# PMIC_RK809_RK3566_LPDDR4.net
KiCad netlist of a schematic drawn in Altium Designer
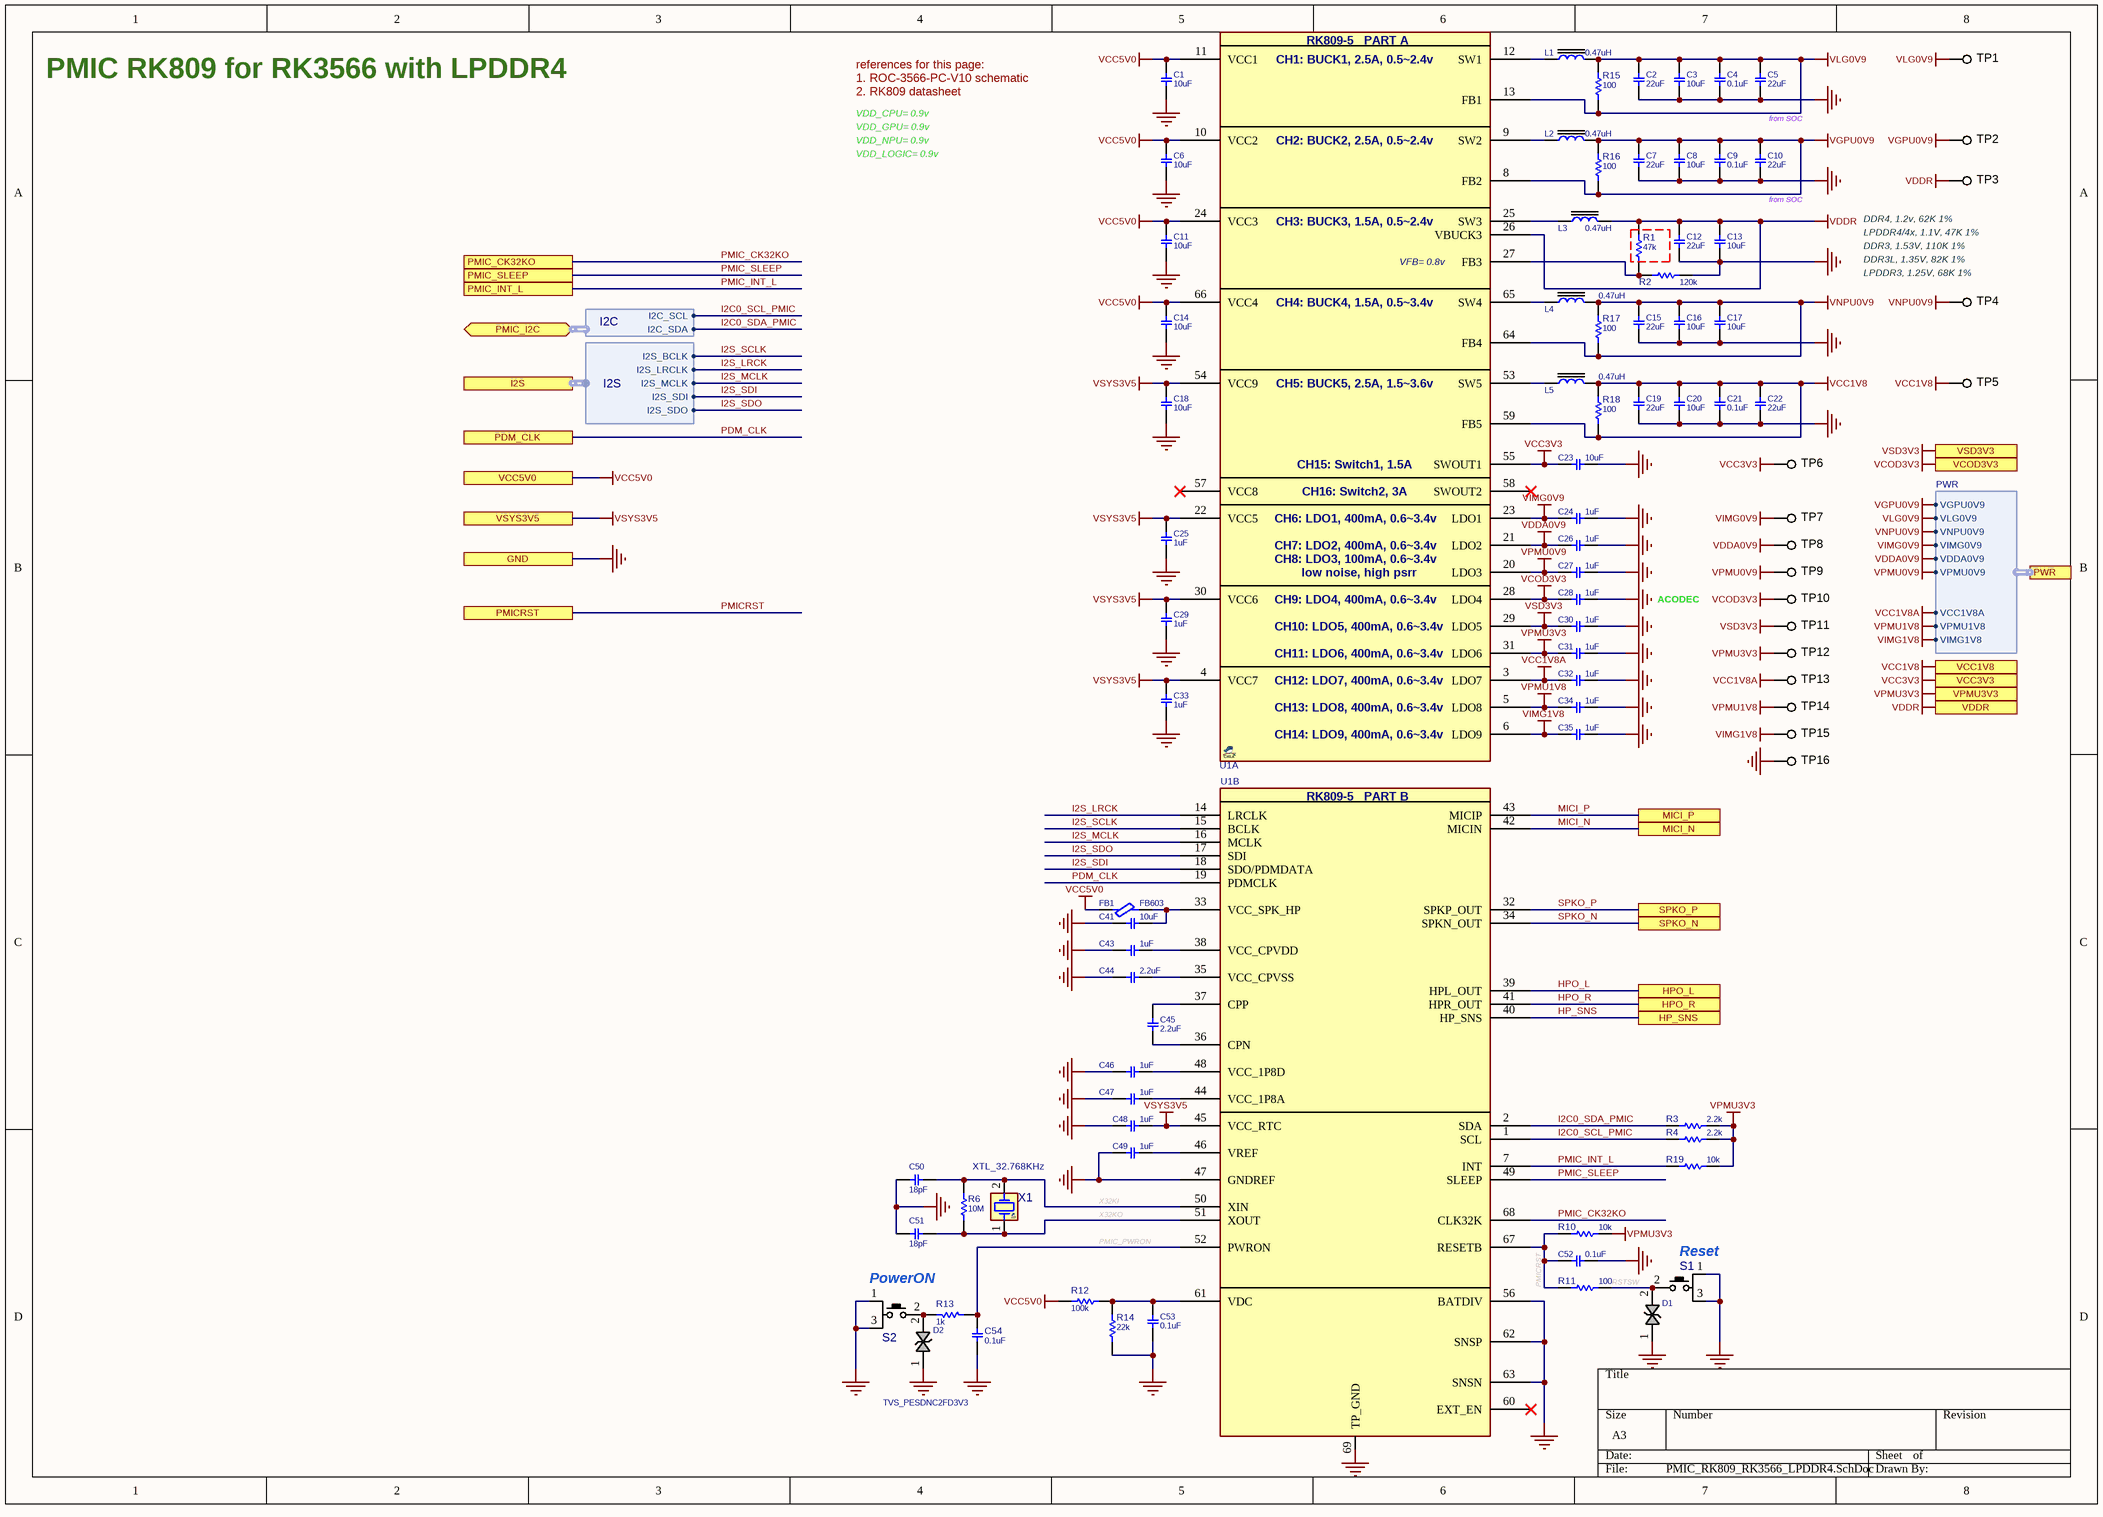
[diagram p0: PMIC_RK809_RK3566_LPDDR4.SchDoc]

(export (version "E")
  (design (tool "Eeschema 10.0.6"))
  (components
    (comp (ref "C1")
      (value "10uF")
      (footprint "C0402")
      (description "CAP, MLCC")
      (fields (field (name "MANF_P#") "CL05A106MP5NUNC") (field (name "MANF") "Samsung"))
      (libsource (lib "passive_smd") (part "CAP_SMD_MLCC"))
    )
    (comp (ref "C2")
      (value "22uF")
      (footprint "C0402")
      (description "CAP, MLCC")
      (fields (field (name "MANF_P#") "GRM158R61A226ME15") (field (name "MANF") "Murata"))
      (libsource (lib "passive_smd") (part "CAP_SMD_MLCC"))
    )
    (comp (ref "C3")
      (value "10uF")
      (footprint "C0402")
      (description "CAP, MLCC")
      (fields (field (name "MANF_P#") "CL05A106MP5NUNC") (field (name "MANF") "Samsung"))
      (libsource (lib "passive_smd") (part "CAP_SMD_MLCC"))
    )
    (comp (ref "C4")
      (value "0.1uF")
      (footprint "C0402")
      (description "CAP, MLCC")
      (fields (field (name "MANF_P#") "GRM155R61E104") (field (name "MANF") "Murata"))
      (libsource (lib "passive_smd") (part "CAP_SMD_MLCC"))
    )
    (comp (ref "C5")
      (value "22uF")
      (footprint "C0402")
      (description "CAP, MLCC")
      (fields (field (name "MANF_P#") "GRM158R61A226ME15") (field (name "MANF") "Murata"))
      (libsource (lib "passive_smd") (part "CAP_SMD_MLCC"))
    )
    (comp (ref "C6")
      (value "10uF")
      (footprint "C0402")
      (description "CAP, MLCC")
      (fields (field (name "MANF_P#") "CL05A106MP5NUNC") (field (name "MANF") "Samsung"))
      (libsource (lib "passive_smd") (part "CAP_SMD_MLCC"))
    )
    (comp (ref "C7")
      (value "22uF")
      (footprint "C0402")
      (description "CAP, MLCC")
      (fields (field (name "MANF_P#") "GRM158R61A226ME15") (field (name "MANF") "Murata"))
      (libsource (lib "passive_smd") (part "CAP_SMD_MLCC"))
    )
    (comp (ref "C8")
      (value "10uF")
      (footprint "C0402")
      (description "CAP, MLCC")
      (fields (field (name "MANF_P#") "CL05A106MP5NUNC") (field (name "MANF") "Samsung"))
      (libsource (lib "passive_smd") (part "CAP_SMD_MLCC"))
    )
    (comp (ref "C9")
      (value "0.1uF")
      (footprint "C0402")
      (description "CAP, MLCC")
      (fields (field (name "MANF_P#") "GRM155R61E104") (field (name "MANF") "Murata"))
      (libsource (lib "passive_smd") (part "CAP_SMD_MLCC"))
    )
    (comp (ref "C10")
      (value "22uF")
      (footprint "C0402")
      (description "CAP, MLCC")
      (fields (field (name "MANF_P#") "GRM158R61A226ME15") (field (name "MANF") "Murata"))
      (libsource (lib "passive_smd") (part "CAP_SMD_MLCC"))
    )
    (comp (ref "C11")
      (value "10uF")
      (footprint "C0402")
      (description "CAP, MLCC")
      (fields (field (name "MANF_P#") "CL05A106MP5NUNC") (field (name "MANF") "Samsung"))
      (libsource (lib "passive_smd") (part "CAP_SMD_MLCC"))
    )
    (comp (ref "C12")
      (value "22uF")
      (footprint "C0402")
      (description "CAP, MLCC")
      (fields (field (name "MANF_P#") "GRM158R61A226ME15") (field (name "MANF") "Murata"))
      (libsource (lib "passive_smd") (part "CAP_SMD_MLCC"))
    )
    (comp (ref "C13")
      (value "10uF")
      (footprint "C0402")
      (description "CAP, MLCC")
      (fields (field (name "MANF_P#") "CL05A106MP5NUNC") (field (name "MANF") "Samsung"))
      (libsource (lib "passive_smd") (part "CAP_SMD_MLCC"))
    )
    (comp (ref "C14")
      (value "10uF")
      (footprint "C0402")
      (description "CAP, MLCC")
      (fields (field (name "MANF_P#") "CL05A106MP5NUNC") (field (name "MANF") "Samsung"))
      (libsource (lib "passive_smd") (part "CAP_SMD_MLCC"))
    )
    (comp (ref "C15")
      (value "22uF")
      (footprint "C0402")
      (description "CAP, MLCC")
      (fields (field (name "MANF_P#") "GRM158R61A226ME15") (field (name "MANF") "Murata"))
      (libsource (lib "passive_smd") (part "CAP_SMD_MLCC"))
    )
    (comp (ref "C16")
      (value "10uF")
      (footprint "C0402")
      (description "CAP, MLCC")
      (fields (field (name "MANF_P#") "CL05A106MP5NUNC") (field (name "MANF") "Samsung"))
      (libsource (lib "passive_smd") (part "CAP_SMD_MLCC"))
    )
    (comp (ref "C17")
      (value "10uF")
      (footprint "C0402")
      (description "CAP, MLCC")
      (fields (field (name "MANF_P#") "CL05A106MP5NUNC") (field (name "MANF") "Samsung"))
      (libsource (lib "passive_smd") (part "CAP_SMD_MLCC"))
    )
    (comp (ref "C18")
      (value "10uF")
      (footprint "C0402")
      (description "CAP, MLCC")
      (fields (field (name "MANF_P#") "CL05A106MP5NUNC") (field (name "MANF") "Samsung"))
      (libsource (lib "passive_smd") (part "CAP_SMD_MLCC"))
    )
    (comp (ref "C19")
      (value "22uF")
      (footprint "C0402")
      (description "CAP, MLCC")
      (fields (field (name "MANF_P#") "GRM158R61A226ME15") (field (name "MANF") "Murata"))
      (libsource (lib "passive_smd") (part "CAP_SMD_MLCC"))
    )
    (comp (ref "C20")
      (value "10uF")
      (footprint "C0402")
      (description "CAP, MLCC")
      (fields (field (name "MANF_P#") "CL05A106MP5NUNC") (field (name "MANF") "Samsung"))
      (libsource (lib "passive_smd") (part "CAP_SMD_MLCC"))
    )
    (comp (ref "C21")
      (value "0.1uF")
      (footprint "C0402")
      (description "CAP, MLCC")
      (fields (field (name "MANF_P#") "GRM155R61E104") (field (name "MANF") "Murata"))
      (libsource (lib "passive_smd") (part "CAP_SMD_MLCC"))
    )
    (comp (ref "C22")
      (value "22uF")
      (footprint "C0402")
      (description "CAP, MLCC")
      (fields (field (name "MANF_P#") "GRM158R61A226ME15") (field (name "MANF") "Murata"))
      (libsource (lib "passive_smd") (part "CAP_SMD_MLCC"))
    )
    (comp (ref "C23")
      (value "10uF")
      (footprint "C0402")
      (description "CAP, MLCC")
      (fields (field (name "MANF_P#") "CL05A106MP5NUNC") (field (name "MANF") "Samsung"))
      (libsource (lib "passive_smd") (part "CAP_SMD_MLCC"))
    )
    (comp (ref "C24")
      (value "1uF")
      (footprint "C0402")
      (description "CAP, MLCC")
      (fields (field (name "MANF_P#") "CL05A105KO5NNND") (field (name "MANF") "Samsung"))
      (libsource (lib "passive_smd") (part "CAP_SMD_MLCC"))
    )
    (comp (ref "C25")
      (value "1uF")
      (footprint "C0402")
      (description "CAP, MLCC")
      (fields (field (name "MANF_P#") "CL05A105KO5NNND") (field (name "MANF") "Samsung"))
      (libsource (lib "passive_smd") (part "CAP_SMD_MLCC"))
    )
    (comp (ref "C26")
      (value "1uF")
      (footprint "C0402")
      (description "CAP, MLCC")
      (fields (field (name "MANF_P#") "CL05A105KO5NNND") (field (name "MANF") "Samsung"))
      (libsource (lib "passive_smd") (part "CAP_SMD_MLCC"))
    )
    (comp (ref "C27")
      (value "1uF")
      (footprint "C0402")
      (description "CAP, MLCC")
      (fields (field (name "MANF_P#") "CL05A105KO5NNND") (field (name "MANF") "Samsung"))
      (libsource (lib "passive_smd") (part "CAP_SMD_MLCC"))
    )
    (comp (ref "C28")
      (value "1uF")
      (footprint "C0402")
      (description "CAP, MLCC")
      (fields (field (name "MANF_P#") "CL05A105KO5NNND") (field (name "MANF") "Samsung"))
      (libsource (lib "passive_smd") (part "CAP_SMD_MLCC"))
    )
    (comp (ref "C29")
      (value "1uF")
      (footprint "C0402")
      (description "CAP, MLCC")
      (fields (field (name "MANF_P#") "CL05A105KO5NNND") (field (name "MANF") "Samsung"))
      (libsource (lib "passive_smd") (part "CAP_SMD_MLCC"))
    )
    (comp (ref "C30")
      (value "1uF")
      (footprint "C0402")
      (description "CAP, MLCC")
      (fields (field (name "MANF_P#") "CL05A105KO5NNND") (field (name "MANF") "Samsung"))
      (libsource (lib "passive_smd") (part "CAP_SMD_MLCC"))
    )
    (comp (ref "C31")
      (value "1uF")
      (footprint "C0402")
      (description "CAP, MLCC")
      (fields (field (name "MANF_P#") "CL05A105KO5NNND") (field (name "MANF") "Samsung"))
      (libsource (lib "passive_smd") (part "CAP_SMD_MLCC"))
    )
    (comp (ref "C32")
      (value "1uF")
      (footprint "C0402")
      (description "CAP, MLCC")
      (fields (field (name "MANF_P#") "CL05A105KO5NNND") (field (name "MANF") "Samsung"))
      (libsource (lib "passive_smd") (part "CAP_SMD_MLCC"))
    )
    (comp (ref "C33")
      (value "1uF")
      (footprint "C0402")
      (description "CAP, MLCC")
      (fields (field (name "MANF_P#") "CL05A105KO5NNND") (field (name "MANF") "Samsung"))
      (libsource (lib "passive_smd") (part "CAP_SMD_MLCC"))
    )
    (comp (ref "C34")
      (value "1uF")
      (footprint "C0402")
      (description "CAP, MLCC")
      (fields (field (name "MANF_P#") "CL05A105KO5NNND") (field (name "MANF") "Samsung"))
      (libsource (lib "passive_smd") (part "CAP_SMD_MLCC"))
    )
    (comp (ref "C35")
      (value "1uF")
      (footprint "C0402")
      (description "CAP, MLCC")
      (fields (field (name "MANF_P#") "CL05A105KO5NNND") (field (name "MANF") "Samsung"))
      (libsource (lib "passive_smd") (part "CAP_SMD_MLCC"))
    )
    (comp (ref "C41")
      (value "10uF")
      (footprint "C0402")
      (description "CAP, MLCC")
      (fields (field (name "MANF_P#") "CL05A106MP5NUNC") (field (name "MANF") "Samsung"))
      (libsource (lib "passive_smd") (part "CAP_SMD_MLCC"))
    )
    (comp (ref "C43")
      (value "1uF")
      (footprint "C0402")
      (description "CAP, MLCC")
      (fields (field (name "MANF_P#") "CL05A105KO5NNND") (field (name "MANF") "Samsung"))
      (libsource (lib "passive_smd") (part "CAP_SMD_MLCC"))
    )
    (comp (ref "C44")
      (value "2.2uF")
      (footprint "C0402")
      (description "CAP, MLCC")
      (fields (field (name "MANF_P#") "CL05A225MP5NNNC") (field (name "MANF") "Samsung"))
      (libsource (lib "passive_smd") (part "CAP_SMD_MLCC"))
    )
    (comp (ref "C45")
      (value "2.2uF")
      (footprint "C0402")
      (description "CAP, MLCC")
      (fields (field (name "MANF_P#") "CL05A225MP5NNNC") (field (name "MANF") "Samsung"))
      (libsource (lib "passive_smd") (part "CAP_SMD_MLCC"))
    )
    (comp (ref "C46")
      (value "1uF")
      (footprint "C0402")
      (description "CAP, MLCC")
      (fields (field (name "MANF_P#") "CL05A105KO5NNND") (field (name "MANF") "Samsung"))
      (libsource (lib "passive_smd") (part "CAP_SMD_MLCC"))
    )
    (comp (ref "C47")
      (value "1uF")
      (footprint "C0402")
      (description "CAP, MLCC")
      (fields (field (name "MANF_P#") "CL05A105KO5NNND") (field (name "MANF") "Samsung"))
      (libsource (lib "passive_smd") (part "CAP_SMD_MLCC"))
    )
    (comp (ref "C48")
      (value "1uF")
      (footprint "C0402")
      (description "CAP, MLCC")
      (fields (field (name "MANF_P#") "CL05A105KO5NNND") (field (name "MANF") "Samsung"))
      (libsource (lib "passive_smd") (part "CAP_SMD_MLCC"))
    )
    (comp (ref "C49")
      (value "1uF")
      (footprint "C0402")
      (description "CAP, MLCC")
      (fields (field (name "MANF_P#") "CL05A105KO5NNND") (field (name "MANF") "Samsung"))
      (libsource (lib "passive_smd") (part "CAP_SMD_MLCC"))
    )
    (comp (ref "C50")
      (value "18pF")
      (footprint "C0402")
      (description "CAP, MLCC")
      (fields (field (name "MANF_P#") "CC0402JRNPO9BN180") (field (name "MANF") "Yageo"))
      (libsource (lib "mlcc_smd_passive") (part "CAP_SMD_MLCC"))
    )
    (comp (ref "C51")
      (value "18pF")
      (footprint "C0402")
      (description "CAP, MLCC")
      (fields (field (name "MANF_P#") "CC0402JRNPO9BN180") (field (name "MANF") "Yageo"))
      (libsource (lib "mlcc_smd_passive") (part "CAP_SMD_MLCC"))
    )
    (comp (ref "C52")
      (value "0.1uF")
      (footprint "C0402")
      (description "CAP, MLCC")
      (fields (field (name "MANF_P#") "GRM155R61E104") (field (name "MANF") "Murata"))
      (libsource (lib "passive_smd") (part "CAP_SMD_MLCC"))
    )
    (comp (ref "C53")
      (value "0.1uF")
      (footprint "C0402")
      (description "CAP, MLCC")
      (fields (field (name "MANF_P#") "GRM155R61E104") (field (name "MANF") "Murata"))
      (libsource (lib "passive_smd") (part "CAP_SMD_MLCC"))
    )
    (comp (ref "C54")
      (value "0.1uF")
      (footprint "C0402")
      (description "CAP, MLCC")
      (fields (field (name "MANF_P#") "GRM155R61E104") (field (name "MANF") "Murata"))
      (libsource (lib "mlcc_smd_passive") (part "CAP_SMD_MLCC_100n50TDK"))
    )
    (comp (ref "D1")
      (value "TVS_PESDNC2FD3V3")
      (footprint "ESD0402")
      (description "TVS, ESD PROTECT, Bidirectional")
      (fields (field (name "MANF_P#") "PESDNC2FD3V3BS"))
      (libsource (lib "protect_tvs_esd_fuse") (part "TVS_PESDNC2FD3V3"))
    )
    (comp (ref "D2")
      (value "TVS_PESDNC2FD3V3")
      (footprint "ESD0402")
      (description "TVS, ESD PROTECT, Bidirectional")
      (fields (field (name "MANF_P#") "PESDNC2FD3V3BS"))
      (libsource (lib "protect_tvs_esd_fuse") (part "TVS_PESDNC2FD3V3"))
    )
    (comp (ref "FB1")
      (value "FB603")
      (footprint "L0603")
      (description "FERRITE_Bead, 0603, 1.3A, 150mOhm, 600@100MHz")
      (fields (field (name "MANF_P#") "ACMS160808A1213A"))
      (libsource (lib "emi_filter") (part "FBEAD_SMD_BLM18KG601"))
    )
    (comp (ref "L1")
      (value "0.47uH")
      (footprint "L0806")
      (description "INDUCTOR")
      (fields (field (name "MANF_P#") "DFE201610E-R47M") (field (name "MANF") "Murata"))
      (libsource (lib "inductor_power") (part "IND_SMD_2.2uH_2.6A"))
    )
    (comp (ref "L2")
      (value "0.47uH")
      (footprint "L0806")
      (description "INDUCTOR")
      (fields (field (name "MANF_P#") "DFE201610E-R47M") (field (name "MANF") "Murata"))
      (libsource (lib "inductor_power") (part "IND_SMD_2.2uH_2.6A"))
    )
    (comp (ref "L3")
      (value "0.47uH")
      (footprint "L0806")
      (description "INDUCTOR")
      (fields (field (name "MANF_P#") "DFE201610E-R47M") (field (name "MANF") "Murata"))
      (libsource (lib "inductor_power") (part "IND_SMD_2.2uH_2.6A"))
    )
    (comp (ref "L4")
      (value "0.47uH")
      (footprint "L0806")
      (description "INDUCTOR")
      (fields (field (name "MANF_P#") "DFE201610E-R47M") (field (name "MANF") "Murata"))
      (libsource (lib "inductor_power") (part "IND_SMD_2.2uH_2.6A"))
    )
    (comp (ref "L5")
      (value "0.47uH")
      (footprint "L0806")
      (description "INDUCTOR")
      (fields (field (name "MANF_P#") "DFE201610E-R47M") (field (name "MANF") "Murata"))
      (libsource (lib "inductor_power") (part "IND_SMD_2.2uH_2.6A"))
    )
    (comp (ref "R1")
      (value "47k")
      (footprint "R0402")
      (description "RESISTOR, SMD")
      (libsource (lib "passive_res_smd") (part "RES_SMD"))
    )
    (comp (ref "R2")
      (value "120k")
      (footprint "R0402")
      (description "RESISTOR, SMD")
      (libsource (lib "passive_res_smd") (part "RES_SMD"))
    )
    (comp (ref "R3")
      (value "2.2k")
      (footprint "R0402")
      (description "RESISTOR, SMD")
      (libsource (lib "passive_res_smd") (part "RES_SMD"))
    )
    (comp (ref "R4")
      (value "2.2k")
      (footprint "R0402")
      (description "RESISTOR, SMD")
      (libsource (lib "passive_res_smd") (part "RES_SMD"))
    )
    (comp (ref "R6")
      (value "10M")
      (footprint "R0402")
      (description "RESISTOR, SMD")
      (libsource (lib "passive_res_smd") (part "RES_SMD"))
    )
    (comp (ref "R10")
      (value "10k")
      (footprint "R0402")
      (description "RESISTOR, SMD")
      (libsource (lib "passive_res_smd") (part "RES_SMD"))
    )
    (comp (ref "R11")
      (value "100")
      (footprint "R0402")
      (description "RESISTOR, SMD")
      (libsource (lib "passive_res_smd") (part "RES_SMD"))
    )
    (comp (ref "R12")
      (value "100k")
      (footprint "R0402")
      (description "RESISTOR, SMD")
      (libsource (lib "passive_res_smd") (part "RES_SMD"))
    )
    (comp (ref "R13")
      (value "1k")
      (footprint "R0402")
      (description "RESISTOR, SMD")
      (libsource (lib "passive_res_smd") (part "RES_SMD"))
    )
    (comp (ref "R14")
      (value "22k")
      (footprint "R0402")
      (description "RESISTOR, SMD")
      (libsource (lib "passive_res_smd") (part "RES_SMD"))
    )
    (comp (ref "R15")
      (value "100")
      (footprint "R0402")
      (description "RESISTOR, SMD")
      (libsource (lib "passive_res_smd") (part "RES_SMD"))
    )
    (comp (ref "R16")
      (value "100")
      (footprint "R0402")
      (description "RESISTOR, SMD")
      (libsource (lib "passive_res_smd") (part "RES_SMD"))
    )
    (comp (ref "R17")
      (value "100")
      (footprint "R0402")
      (description "RESISTOR, SMD")
      (libsource (lib "passive_res_smd") (part "RES_SMD"))
    )
    (comp (ref "R18")
      (value "100")
      (footprint "R0402")
      (description "RESISTOR, SMD")
      (libsource (lib "passive_res_smd") (part "RES_SMD"))
    )
    (comp (ref "R19")
      (value "10k")
      (footprint "R0402")
      (description "RESISTOR, SMD")
      (libsource (lib "passive_res_smd") (part "RES_SMD"))
    )
    (comp (ref "S1")
      (value "PUSHBUTTON")
      (footprint "SWPBS_SPDT_R_EVPAE")
      (description "SWITCH, PUSH BUTTON, TACTILE, THD, SPDT, RIGHT")
      (fields (field (name "MANF") "Panasonic") (field (name "MANF_P#") "EVP-AEBB2A, EVP-AEDB2A, EVP-AEJB2A"))
      (libsource (lib "") (part "SWPBS_SPDT_R_EVPAE_1"))
    )
    (comp (ref "S2")
      (value "PUSHBUTTON")
      (footprint "SWPBS_SPDT_R_EVPAE")
      (description "SWITCH, PUSH BUTTON, TACTILE, THD, SPDT, RIGHT")
      (fields (field (name "MANF") "Panasonic") (field (name "MANF_P#") "EVP-AEBB2A, EVP-AEDB2A, EVP-AEJB2A"))
      (libsource (lib "switch_tact_PUSHB") (part "SWPBS_SPDT_R_EVPAE"))
    )
    (comp (ref "TP1")
      (value "TESTPOINT_SMD")
      (footprint "TPSMD_S1")
      (description "TEST POINT")
      (fields (field (name "MANF") "MANF") (field (name "MANF_P#") "MANF_P#"))
      (libsource (lib "test-tp_jumper") (part "TESTPOINT_SMD"))
    )
    (comp (ref "TP2")
      (value "TESTPOINT_SMD")
      (footprint "TPSMD_S1")
      (description "TEST POINT")
      (fields (field (name "MANF") "MANF") (field (name "MANF_P#") "MANF_P#"))
      (libsource (lib "test-tp_jumper") (part "TESTPOINT_SMD"))
    )
    (comp (ref "TP3")
      (value "TESTPOINT_SMD")
      (footprint "TPSMD_S1")
      (description "TEST POINT")
      (fields (field (name "MANF") "MANF") (field (name "MANF_P#") "MANF_P#"))
      (libsource (lib "test-tp_jumper") (part "TESTPOINT_SMD"))
    )
    (comp (ref "TP4")
      (value "TESTPOINT_SMD")
      (footprint "TPSMD_S1")
      (description "TEST POINT")
      (fields (field (name "MANF") "MANF") (field (name "MANF_P#") "MANF_P#"))
      (libsource (lib "test-tp_jumper") (part "TESTPOINT_SMD"))
    )
    (comp (ref "TP5")
      (value "TESTPOINT_SMD")
      (footprint "TPSMD_S1")
      (description "TEST POINT")
      (fields (field (name "MANF") "MANF") (field (name "MANF_P#") "MANF_P#"))
      (libsource (lib "test-tp_jumper") (part "TESTPOINT_SMD"))
    )
    (comp (ref "TP6")
      (value "TESTPOINT_SMD")
      (footprint "TPSMD_S1")
      (description "TEST POINT")
      (fields (field (name "MANF") "MANF") (field (name "MANF_P#") "MANF_P#"))
      (libsource (lib "test-tp_jumper") (part "TESTPOINT_SMD"))
    )
    (comp (ref "TP7")
      (value "TESTPOINT_SMD")
      (footprint "TPSMD_S1")
      (description "TEST POINT")
      (fields (field (name "MANF") "MANF") (field (name "MANF_P#") "MANF_P#"))
      (libsource (lib "test-tp_jumper") (part "TESTPOINT_SMD"))
    )
    (comp (ref "TP8")
      (value "TESTPOINT_SMD")
      (footprint "TPSMD_S1")
      (description "TEST POINT")
      (fields (field (name "MANF") "MANF") (field (name "MANF_P#") "MANF_P#"))
      (libsource (lib "test-tp_jumper") (part "TESTPOINT_SMD"))
    )
    (comp (ref "TP9")
      (value "TESTPOINT_SMD")
      (footprint "TPSMD_S1")
      (description "TEST POINT")
      (fields (field (name "MANF") "MANF") (field (name "MANF_P#") "MANF_P#"))
      (libsource (lib "test-tp_jumper") (part "TESTPOINT_SMD"))
    )
    (comp (ref "TP10")
      (value "TESTPOINT_SMD")
      (footprint "TPSMD_S1")
      (description "TEST POINT")
      (fields (field (name "MANF") "MANF") (field (name "MANF_P#") "MANF_P#"))
      (libsource (lib "test-tp_jumper") (part "TESTPOINT_SMD"))
    )
    (comp (ref "TP11")
      (value "TESTPOINT_SMD")
      (footprint "TPSMD_S1")
      (description "TEST POINT")
      (fields (field (name "MANF") "MANF") (field (name "MANF_P#") "MANF_P#"))
      (libsource (lib "test-tp_jumper") (part "TESTPOINT_SMD"))
    )
    (comp (ref "TP12")
      (value "TESTPOINT_SMD")
      (footprint "TPSMD_S1")
      (description "TEST POINT")
      (fields (field (name "MANF") "MANF") (field (name "MANF_P#") "MANF_P#"))
      (libsource (lib "test-tp_jumper") (part "TESTPOINT_SMD"))
    )
    (comp (ref "TP13")
      (value "TESTPOINT_SMD")
      (footprint "TPSMD_S1")
      (description "TEST POINT")
      (fields (field (name "MANF") "MANF") (field (name "MANF_P#") "MANF_P#"))
      (libsource (lib "test-tp_jumper") (part "TESTPOINT_SMD"))
    )
    (comp (ref "TP14")
      (value "TESTPOINT_SMD")
      (footprint "TPSMD_S1")
      (description "TEST POINT")
      (fields (field (name "MANF") "MANF") (field (name "MANF_P#") "MANF_P#"))
      (libsource (lib "test-tp_jumper") (part "TESTPOINT_SMD"))
    )
    (comp (ref "TP15")
      (value "TESTPOINT_SMD")
      (footprint "TPSMD_S1")
      (description "TEST POINT")
      (fields (field (name "MANF") "MANF") (field (name "MANF_P#") "MANF_P#"))
      (libsource (lib "test-tp_jumper") (part "TESTPOINT_SMD"))
    )
    (comp (ref "TP16")
      (value "TESTPOINT_SMD")
      (footprint "TPSMD_S1")
      (description "TEST POINT")
      (fields (field (name "MANF") "MANF") (field (name "MANF_P#") "MANF_P#"))
      (libsource (lib "test-tp_jumper") (part "TESTPOINT_SMD"))
    )
    (comp (ref "U1")
      (value "RK809-5")
      (footprint "QFN35_68T")
      (description "IC, Regulator PMIC, for RK3566")
      (fields (field (name "MANF") "Rockchip"))
      (libsource (lib "pwr_reg_pmic") (part "RK809-5_QFN68"))
    )
    (comp (ref "X1")
      (value "XTL_32.768KHz")
      (footprint "XTL_2_1610")
      (description "Crystal, 32.768KHz, 9pF, 20PPM")
      (fields (field (name "MANF") "ABRACON") (field (name "MANF_P#") "ABS05-32.768KHZ-9-T"))
      (libsource (lib "crystal") (part "XTL_2_32.768_1610A"))
    )
  )
  (nets
    (net (code "4") (name "/HPO_L") (class "Default")
      (node (ref "U1") (pin "39") (pinfunction "HPL_OUT_39") (pintype "passive"))
    )
    (net (code "5") (name "/HPO_R") (class "Default")
      (node (ref "U1") (pin "41") (pinfunction "HPR_OUT_41") (pintype "passive"))
    )
    (net (code "6") (name "/HP_SNS") (class "Default")
      (node (ref "U1") (pin "40") (pinfunction "HP_SNS_40") (pintype "passive"))
    )
    (net (code "7") (name "/I2C0_SCL_PMIC") (class "Default")
      (node (ref "R4") (pin "2") (pinfunction "2_2") (pintype "passive"))
      (node (ref "U1") (pin "1") (pinfunction "SCL_1") (pintype "passive"))
    )
    (net (code "8") (name "/I2C0_SDA_PMIC") (class "Default")
      (node (ref "R3") (pin "2") (pinfunction "2_2") (pintype "passive"))
      (node (ref "U1") (pin "2") (pinfunction "SDA_2") (pintype "passive"))
    )
    (net (code "9") (name "/I2S_LRCK") (class "Default")
      (node (ref "U1") (pin "14") (pinfunction "LRCLK_14") (pintype "passive"))
    )
    (net (code "10") (name "/I2S_MCLK") (class "Default")
      (node (ref "U1") (pin "16") (pinfunction "MCLK_16") (pintype "passive"))
    )
    (net (code "11") (name "/I2S_SCLK") (class "Default")
      (node (ref "U1") (pin "15") (pinfunction "BCLK_15") (pintype "passive"))
    )
    (net (code "12") (name "/I2S_SDI") (class "Default")
      (node (ref "U1") (pin "18") (pinfunction "SDO/PDMDATA_18") (pintype "passive"))
    )
    (net (code "13") (name "/I2S_SDO") (class "Default")
      (node (ref "U1") (pin "17") (pinfunction "SDI_17") (pintype "passive"))
    )
    (net (code "14") (name "/MICI_N") (class "Default")
      (node (ref "U1") (pin "42") (pinfunction "MICIN_42") (pintype "passive"))
    )
    (net (code "15") (name "/MICI_P") (class "Default")
      (node (ref "U1") (pin "43") (pinfunction "MICIP_43") (pintype "passive"))
    )
    (net (code "16") (name "/PDM_CLK") (class "Default")
      (node (ref "U1") (pin "19") (pinfunction "PDMCLK_19") (pintype "passive"))
    )
    (net (code "17") (name "/PMICRST") (class "Default")
      (node (ref "C52") (pin "1") (pinfunction "1_1") (pintype "passive"))
      (node (ref "R10") (pin "1") (pinfunction "1_1") (pintype "passive"))
      (node (ref "R11") (pin "1") (pinfunction "1_1") (pintype "passive"))
      (node (ref "U1") (pin "67") (pinfunction "RESETB_67") (pintype "passive"))
    )
    (net (code "18") (name "/PMIC_CK32KO") (class "Default")
      (node (ref "U1") (pin "68") (pinfunction "CLK32K_68") (pintype "passive"))
    )
    (net (code "19") (name "/PMIC_INT_L") (class "Default")
      (node (ref "R19") (pin "1") (pinfunction "1_1") (pintype "passive"))
      (node (ref "U1") (pin "7") (pinfunction "INT_7") (pintype "passive"))
    )
    (net (code "20") (name "/PMIC_PWRON") (class "Default")
      (node (ref "C54") (pin "1") (pinfunction "1_1") (pintype "passive"))
      (node (ref "R13") (pin "2") (pinfunction "2_2") (pintype "passive"))
      (node (ref "U1") (pin "52") (pinfunction "PWRON_52") (pintype "passive"))
    )
    (net (code "21") (name "/PMIC_SLEEP") (class "Default")
      (node (ref "U1") (pin "49") (pinfunction "SLEEP_49") (pintype "passive"))
    )
    (net (code "22") (name "/RSTSW") (class "Default")
      (node (ref "D1") (pin "2") (pinfunction "2_2") (pintype "passive"))
      (node (ref "R11") (pin "2") (pinfunction "2_2") (pintype "passive"))
      (node (ref "S1") (pin "2") (pinfunction "2_2") (pintype "passive"))
    )
    (net (code "23") (name "/SPKO_N") (class "Default")
      (node (ref "U1") (pin "34") (pinfunction "SPKN_OUT_34") (pintype "passive"))
    )
    (net (code "24") (name "/SPKO_P") (class "Default")
      (node (ref "U1") (pin "32") (pinfunction "SPKP_OUT_32") (pintype "passive"))
    )
    (net (code "25") (name "/X32KI") (class "Default")
      (node (ref "C50") (pin "1") (pinfunction "1_1") (pintype "passive"))
      (node (ref "R6") (pin "2") (pinfunction "2_2") (pintype "passive"))
      (node (ref "U1") (pin "50") (pinfunction "XIN_50") (pintype "passive"))
      (node (ref "X1") (pin "2") (pinfunction "OSC2_2") (pintype "passive"))
    )
    (net (code "26") (name "/X32KO") (class "Default")
      (node (ref "C51") (pin "1") (pinfunction "1_1") (pintype "passive"))
      (node (ref "R6") (pin "1") (pinfunction "1_1") (pintype "passive"))
      (node (ref "U1") (pin "51") (pinfunction "XOUT_51") (pintype "passive"))
      (node (ref "X1") (pin "1") (pinfunction "OSC1_1") (pintype "passive"))
    )
    (net (code "30") (name "GND") (class "Default")
      (node (ref "C1") (pin "1") (pinfunction "1_1") (pintype "passive"))
      (node (ref "C10") (pin "1") (pinfunction "1_1") (pintype "passive"))
      (node (ref "C11") (pin "1") (pinfunction "1_1") (pintype "passive"))
      (node (ref "C12") (pin "1") (pinfunction "1_1") (pintype "passive"))
      (node (ref "C13") (pin "1") (pinfunction "1_1") (pintype "passive"))
      (node (ref "C14") (pin "1") (pinfunction "1_1") (pintype "passive"))
      (node (ref "C15") (pin "1") (pinfunction "1_1") (pintype "passive"))
      (node (ref "C16") (pin "1") (pinfunction "1_1") (pintype "passive"))
      (node (ref "C17") (pin "1") (pinfunction "1_1") (pintype "passive"))
      (node (ref "C18") (pin "1") (pinfunction "1_1") (pintype "passive"))
      (node (ref "C19") (pin "1") (pinfunction "1_1") (pintype "passive"))
      (node (ref "C2") (pin "1") (pinfunction "1_1") (pintype "passive"))
      (node (ref "C20") (pin "1") (pinfunction "1_1") (pintype "passive"))
      (node (ref "C21") (pin "1") (pinfunction "1_1") (pintype "passive"))
      (node (ref "C22") (pin "1") (pinfunction "1_1") (pintype "passive"))
      (node (ref "C23") (pin "1") (pinfunction "1_1") (pintype "passive"))
      (node (ref "C24") (pin "1") (pinfunction "1_1") (pintype "passive"))
      (node (ref "C25") (pin "1") (pinfunction "1_1") (pintype "passive"))
      (node (ref "C26") (pin "1") (pinfunction "1_1") (pintype "passive"))
      (node (ref "C27") (pin "1") (pinfunction "1_1") (pintype "passive"))
      (node (ref "C28") (pin "1") (pinfunction "1_1") (pintype "passive"))
      (node (ref "C29") (pin "1") (pinfunction "1_1") (pintype "passive"))
      (node (ref "C3") (pin "1") (pinfunction "1_1") (pintype "passive"))
      (node (ref "C30") (pin "1") (pinfunction "1_1") (pintype "passive"))
      (node (ref "C31") (pin "1") (pinfunction "1_1") (pintype "passive"))
      (node (ref "C32") (pin "1") (pinfunction "1_1") (pintype "passive"))
      (node (ref "C33") (pin "1") (pinfunction "1_1") (pintype "passive"))
      (node (ref "C34") (pin "1") (pinfunction "1_1") (pintype "passive"))
      (node (ref "C35") (pin "1") (pinfunction "1_1") (pintype "passive"))
      (node (ref "C4") (pin "1") (pinfunction "1_1") (pintype "passive"))
      (node (ref "C41") (pin "1") (pinfunction "1_1") (pintype "passive"))
      (node (ref "C43") (pin "2") (pinfunction "2_2") (pintype "passive"))
      (node (ref "C44") (pin "2") (pinfunction "2_2") (pintype "passive"))
      (node (ref "C46") (pin "2") (pinfunction "2_2") (pintype "passive"))
      (node (ref "C47") (pin "2") (pinfunction "2_2") (pintype "passive"))
      (node (ref "C48") (pin "2") (pinfunction "2_2") (pintype "passive"))
      (node (ref "C49") (pin "2") (pinfunction "2_2") (pintype "passive"))
      (node (ref "C5") (pin "1") (pinfunction "1_1") (pintype "passive"))
      (node (ref "C50") (pin "2") (pinfunction "2_2") (pintype "passive"))
      (node (ref "C51") (pin "2") (pinfunction "2_2") (pintype "passive"))
      (node (ref "C52") (pin "2") (pinfunction "2_2") (pintype "passive"))
      (node (ref "C53") (pin "1") (pinfunction "1_1") (pintype "passive"))
      (node (ref "C54") (pin "2") (pinfunction "2_2") (pintype "passive"))
      (node (ref "C6") (pin "1") (pinfunction "1_1") (pintype "passive"))
      (node (ref "C7") (pin "1") (pinfunction "1_1") (pintype "passive"))
      (node (ref "C8") (pin "1") (pinfunction "1_1") (pintype "passive"))
      (node (ref "C9") (pin "1") (pinfunction "1_1") (pintype "passive"))
      (node (ref "D1") (pin "1") (pinfunction "1_1") (pintype "passive"))
      (node (ref "D2") (pin "1") (pinfunction "1_1") (pintype "passive"))
      (node (ref "R14") (pin "2") (pinfunction "2_2") (pintype "passive"))
      (node (ref "R2") (pin "1") (pinfunction "1_1") (pintype "passive"))
      (node (ref "S1") (pin "1") (pinfunction "1_1") (pintype "passive"))
      (node (ref "S1") (pin "3") (pinfunction "3_3") (pintype "passive"))
      (node (ref "S2") (pin "1") (pinfunction "1_1") (pintype "passive"))
      (node (ref "S2") (pin "3") (pinfunction "3_3") (pintype "passive"))
      (node (ref "TP16") (pin "1") (pinfunction "1_1") (pintype "passive"))
      (node (ref "U1") (pin "47") (pinfunction "GNDREF_47") (pintype "passive"))
      (node (ref "U1") (pin "56") (pinfunction "BATDIV_56") (pintype "passive"))
      (node (ref "U1") (pin "62") (pinfunction "SNSP_62") (pintype "passive"))
      (node (ref "U1") (pin "63") (pinfunction "SNSN_63") (pintype "passive"))
      (node (ref "U1") (pin "69") (pinfunction "TP_GND_69") (pintype "passive"))
    )
    (net (code "31") (name "Net-(D2-Pad2)") (class "Default")
      (node (ref "D2") (pin "2") (pinfunction "2_2") (pintype "passive"))
      (node (ref "R13") (pin "1") (pinfunction "1_1") (pintype "passive"))
      (node (ref "S2") (pin "2") (pinfunction "2_2") (pintype "passive"))
    )
    (net (code "32") (name "Net-(U1A-FB3)") (class "Default")
      (node (ref "R1") (pin "1") (pinfunction "1_1") (pintype "passive"))
      (node (ref "R2") (pin "2") (pinfunction "2_2") (pintype "passive"))
      (node (ref "U1") (pin "27") (pinfunction "FB3_27") (pintype "passive"))
    )
    (net (code "33") (name "Net-(U1A-SW1)") (class "Default")
      (node (ref "L1") (pin "1") (pinfunction "1_1") (pintype "passive"))
      (node (ref "U1") (pin "12") (pinfunction "SW1_12") (pintype "passive"))
    )
    (net (code "34") (name "Net-(U1A-SW2)") (class "Default")
      (node (ref "L2") (pin "1") (pinfunction "1_1") (pintype "passive"))
      (node (ref "U1") (pin "9") (pinfunction "SW2_9") (pintype "passive"))
    )
    (net (code "35") (name "Net-(U1A-SW3)") (class "Default")
      (node (ref "L3") (pin "1") (pinfunction "1_1") (pintype "passive"))
      (node (ref "U1") (pin "25") (pinfunction "SW3_25") (pintype "passive"))
    )
    (net (code "36") (name "Net-(U1A-SW4)") (class "Default")
      (node (ref "L4") (pin "1") (pinfunction "1_1") (pintype "passive"))
      (node (ref "U1") (pin "65") (pinfunction "SW4_65") (pintype "passive"))
    )
    (net (code "37") (name "Net-(U1A-SW5)") (class "Default")
      (node (ref "L5") (pin "1") (pinfunction "1_1") (pintype "passive"))
      (node (ref "U1") (pin "53") (pinfunction "SW5_53") (pintype "passive"))
    )
    (net (code "38") (name "Net-(U1B-CPN)") (class "Default")
      (node (ref "C45") (pin "1") (pinfunction "1_1") (pintype "passive"))
      (node (ref "U1") (pin "36") (pinfunction "CPN_36") (pintype "passive"))
    )
    (net (code "39") (name "Net-(U1B-CPP)") (class "Default")
      (node (ref "C45") (pin "2") (pinfunction "2_2") (pintype "passive"))
      (node (ref "U1") (pin "37") (pinfunction "CPP_37") (pintype "passive"))
    )
    (net (code "40") (name "Net-(U1B-VCC_1P8A)") (class "Default")
      (node (ref "C47") (pin "1") (pinfunction "1_1") (pintype "passive"))
      (node (ref "U1") (pin "44") (pinfunction "VCC_1P8A_44") (pintype "passive"))
    )
    (net (code "41") (name "Net-(U1B-VCC_1P8D)") (class "Default")
      (node (ref "C46") (pin "1") (pinfunction "1_1") (pintype "passive"))
      (node (ref "U1") (pin "48") (pinfunction "VCC_1P8D_48") (pintype "passive"))
    )
    (net (code "42") (name "Net-(U1B-VCC_CPVDD)") (class "Default")
      (node (ref "C43") (pin "1") (pinfunction "1_1") (pintype "passive"))
      (node (ref "U1") (pin "38") (pinfunction "VCC_CPVDD_38") (pintype "passive"))
    )
    (net (code "43") (name "Net-(U1B-VCC_CPVSS)") (class "Default")
      (node (ref "C44") (pin "1") (pinfunction "1_1") (pintype "passive"))
      (node (ref "U1") (pin "35") (pinfunction "VCC_CPVSS_35") (pintype "passive"))
    )
    (net (code "44") (name "Net-(U1B-VCC_SPK_HP)") (class "Default")
      (node (ref "C41") (pin "2") (pinfunction "2_2") (pintype "passive"))
      (node (ref "FB1") (pin "2") (pinfunction "2_2") (pintype "passive"))
      (node (ref "U1") (pin "33") (pinfunction "VCC_SPK_HP_33") (pintype "passive"))
    )
    (net (code "45") (name "Net-(U1B-VDC)") (class "Default")
      (node (ref "C53") (pin "2") (pinfunction "2_2") (pintype "passive"))
      (node (ref "R12") (pin "1") (pinfunction "1_1") (pintype "passive"))
      (node (ref "R14") (pin "1") (pinfunction "1_1") (pintype "passive"))
      (node (ref "U1") (pin "61") (pinfunction "VDC_61") (pintype "passive"))
    )
    (net (code "46") (name "Net-(U1B-VREF)") (class "Default")
      (node (ref "C49") (pin "1") (pinfunction "1_1") (pintype "passive"))
      (node (ref "U1") (pin "46") (pinfunction "VREF_46") (pintype "passive"))
    )
    (net (code "47") (name "VCC1V8") (class "Default")
      (node (ref "C19") (pin "2") (pinfunction "2_2") (pintype "passive"))
      (node (ref "C20") (pin "2") (pinfunction "2_2") (pintype "passive"))
      (node (ref "C21") (pin "2") (pinfunction "2_2") (pintype "passive"))
      (node (ref "C22") (pin "2") (pinfunction "2_2") (pintype "passive"))
      (node (ref "L5") (pin "2") (pinfunction "2_2") (pintype "passive"))
      (node (ref "R18") (pin "1") (pinfunction "1_1") (pintype "passive"))
      (node (ref "R18") (pin "2") (pinfunction "2_2") (pintype "passive"))
      (node (ref "TP5") (pin "1") (pinfunction "1_1") (pintype "passive"))
      (node (ref "U1") (pin "59") (pinfunction "FB5_59") (pintype "passive"))
    )
    (net (code "48") (name "VCC1V8A") (class "Default")
      (node (ref "C32") (pin "2") (pinfunction "2_2") (pintype "passive"))
      (node (ref "TP13") (pin "1") (pinfunction "1_1") (pintype "passive"))
      (node (ref "U1") (pin "3") (pinfunction "LDO7_3") (pintype "passive"))
    )
    (net (code "49") (name "VCC3V3") (class "Default")
      (node (ref "C23") (pin "2") (pinfunction "2_2") (pintype "passive"))
      (node (ref "TP6") (pin "1") (pinfunction "1_1") (pintype "passive"))
      (node (ref "U1") (pin "55") (pinfunction "SWOUT1_55") (pintype "passive"))
    )
    (net (code "50") (name "VCC5V0") (class "Default")
      (node (ref "C1") (pin "2") (pinfunction "2_2") (pintype "passive"))
      (node (ref "C11") (pin "2") (pinfunction "2_2") (pintype "passive"))
      (node (ref "C14") (pin "2") (pinfunction "2_2") (pintype "passive"))
      (node (ref "C6") (pin "2") (pinfunction "2_2") (pintype "passive"))
      (node (ref "FB1") (pin "1") (pinfunction "1_1") (pintype "passive"))
      (node (ref "R12") (pin "2") (pinfunction "2_2") (pintype "passive"))
      (node (ref "U1") (pin "10") (pinfunction "VCC2_10") (pintype "passive"))
      (node (ref "U1") (pin "11") (pinfunction "VCC1_11") (pintype "passive"))
      (node (ref "U1") (pin "24") (pinfunction "VCC3_24") (pintype "passive"))
      (node (ref "U1") (pin "66") (pinfunction "VCC4_66") (pintype "passive"))
    )
    (net (code "51") (name "VCOD3V3") (class "Default")
      (node (ref "C28") (pin "2") (pinfunction "2_2") (pintype "passive"))
      (node (ref "TP10") (pin "1") (pinfunction "1_1") (pintype "passive"))
      (node (ref "U1") (pin "28") (pinfunction "LDO4_28") (pintype "passive"))
    )
    (net (code "52") (name "VDDA0V9") (class "Default")
      (node (ref "C26") (pin "2") (pinfunction "2_2") (pintype "passive"))
      (node (ref "TP8") (pin "1") (pinfunction "1_1") (pintype "passive"))
      (node (ref "U1") (pin "21") (pinfunction "LDO2_21") (pintype "passive"))
    )
    (net (code "53") (name "VDDR") (class "Default")
      (node (ref "C12") (pin "2") (pinfunction "2_2") (pintype "passive"))
      (node (ref "C13") (pin "2") (pinfunction "2_2") (pintype "passive"))
      (node (ref "L3") (pin "2") (pinfunction "2_2") (pintype "passive"))
      (node (ref "R1") (pin "2") (pinfunction "2_2") (pintype "passive"))
      (node (ref "TP3") (pin "1") (pinfunction "1_1") (pintype "passive"))
      (node (ref "U1") (pin "26") (pinfunction "VBUCK3_26") (pintype "passive"))
    )
    (net (code "54") (name "VGPU0V9") (class "Default")
      (node (ref "C10") (pin "2") (pinfunction "2_2") (pintype "passive"))
      (node (ref "C7") (pin "2") (pinfunction "2_2") (pintype "passive"))
      (node (ref "C8") (pin "2") (pinfunction "2_2") (pintype "passive"))
      (node (ref "C9") (pin "2") (pinfunction "2_2") (pintype "passive"))
      (node (ref "L2") (pin "2") (pinfunction "2_2") (pintype "passive"))
      (node (ref "R16") (pin "1") (pinfunction "1_1") (pintype "passive"))
      (node (ref "R16") (pin "2") (pinfunction "2_2") (pintype "passive"))
      (node (ref "TP2") (pin "1") (pinfunction "1_1") (pintype "passive"))
      (node (ref "U1") (pin "8") (pinfunction "FB2_8") (pintype "passive"))
    )
    (net (code "55") (name "VIMG0V9") (class "Default")
      (node (ref "C24") (pin "2") (pinfunction "2_2") (pintype "passive"))
      (node (ref "TP7") (pin "1") (pinfunction "1_1") (pintype "passive"))
      (node (ref "U1") (pin "23") (pinfunction "LDO1_23") (pintype "passive"))
    )
    (net (code "56") (name "VIMG1V8") (class "Default")
      (node (ref "C35") (pin "2") (pinfunction "2_2") (pintype "passive"))
      (node (ref "TP15") (pin "1") (pinfunction "1_1") (pintype "passive"))
      (node (ref "U1") (pin "6") (pinfunction "LDO9_6") (pintype "passive"))
    )
    (net (code "57") (name "VLG0V9") (class "Default")
      (node (ref "C2") (pin "2") (pinfunction "2_2") (pintype "passive"))
      (node (ref "C3") (pin "2") (pinfunction "2_2") (pintype "passive"))
      (node (ref "C4") (pin "2") (pinfunction "2_2") (pintype "passive"))
      (node (ref "C5") (pin "2") (pinfunction "2_2") (pintype "passive"))
      (node (ref "L1") (pin "2") (pinfunction "2_2") (pintype "passive"))
      (node (ref "R15") (pin "1") (pinfunction "1_1") (pintype "passive"))
      (node (ref "R15") (pin "2") (pinfunction "2_2") (pintype "passive"))
      (node (ref "TP1") (pin "1") (pinfunction "1_1") (pintype "passive"))
      (node (ref "U1") (pin "13") (pinfunction "FB1_13") (pintype "passive"))
    )
    (net (code "58") (name "VNPU0V9") (class "Default")
      (node (ref "C15") (pin "2") (pinfunction "2_2") (pintype "passive"))
      (node (ref "C16") (pin "2") (pinfunction "2_2") (pintype "passive"))
      (node (ref "C17") (pin "2") (pinfunction "2_2") (pintype "passive"))
      (node (ref "L4") (pin "2") (pinfunction "2_2") (pintype "passive"))
      (node (ref "R17") (pin "1") (pinfunction "1_1") (pintype "passive"))
      (node (ref "R17") (pin "2") (pinfunction "2_2") (pintype "passive"))
      (node (ref "TP4") (pin "1") (pinfunction "1_1") (pintype "passive"))
      (node (ref "U1") (pin "64") (pinfunction "FB4_64") (pintype "passive"))
    )
    (net (code "59") (name "VPMU0V9") (class "Default")
      (node (ref "C27") (pin "2") (pinfunction "2_2") (pintype "passive"))
      (node (ref "TP9") (pin "1") (pinfunction "1_1") (pintype "passive"))
      (node (ref "U1") (pin "20") (pinfunction "LDO3_20") (pintype "passive"))
    )
    (net (code "60") (name "VPMU1V8") (class "Default")
      (node (ref "C34") (pin "2") (pinfunction "2_2") (pintype "passive"))
      (node (ref "TP14") (pin "1") (pinfunction "1_1") (pintype "passive"))
      (node (ref "U1") (pin "5") (pinfunction "LDO8_5") (pintype "passive"))
    )
    (net (code "61") (name "VPMU3V3") (class "Default")
      (node (ref "C31") (pin "2") (pinfunction "2_2") (pintype "passive"))
      (node (ref "R10") (pin "2") (pinfunction "2_2") (pintype "passive"))
      (node (ref "R19") (pin "2") (pinfunction "2_2") (pintype "passive"))
      (node (ref "R3") (pin "1") (pinfunction "1_1") (pintype "passive"))
      (node (ref "R4") (pin "1") (pinfunction "1_1") (pintype "passive"))
      (node (ref "TP12") (pin "1") (pinfunction "1_1") (pintype "passive"))
      (node (ref "U1") (pin "31") (pinfunction "LDO6_31") (pintype "passive"))
    )
    (net (code "62") (name "VSD3V3") (class "Default")
      (node (ref "C30") (pin "2") (pinfunction "2_2") (pintype "passive"))
      (node (ref "TP11") (pin "1") (pinfunction "1_1") (pintype "passive"))
      (node (ref "U1") (pin "29") (pinfunction "LDO5_29") (pintype "passive"))
    )
    (net (code "63") (name "VSYS3V5") (class "Default")
      (node (ref "C18") (pin "2") (pinfunction "2_2") (pintype "passive"))
      (node (ref "C25") (pin "2") (pinfunction "2_2") (pintype "passive"))
      (node (ref "C29") (pin "2") (pinfunction "2_2") (pintype "passive"))
      (node (ref "C33") (pin "2") (pinfunction "2_2") (pintype "passive"))
      (node (ref "C48") (pin "1") (pinfunction "1_1") (pintype "passive"))
      (node (ref "U1") (pin "22") (pinfunction "VCC5_22") (pintype "passive"))
      (node (ref "U1") (pin "30") (pinfunction "VCC6_30") (pintype "passive"))
      (node (ref "U1") (pin "4") (pinfunction "VCC7_4") (pintype "passive"))
      (node (ref "U1") (pin "45") (pinfunction "VCC_RTC_45") (pintype "passive"))
      (node (ref "U1") (pin "54") (pinfunction "VCC9_54") (pintype "passive"))
    )
    (net (code "64") (name "unconnected-(U1A-SWOUT2-Pad58)") (class "Default")
      (node (ref "U1") (pin "58") (pinfunction "SWOUT2_58") (pintype "passive+no_connect"))
    )
    (net (code "65") (name "unconnected-(U1A-VCC8-Pad57)") (class "Default")
      (node (ref "U1") (pin "57") (pinfunction "VCC8_57") (pintype "passive+no_connect"))
    )
    (net (code "66") (name "unconnected-(U1B-EXT_EN-Pad60)") (class "Default")
      (node (ref "U1") (pin "60") (pinfunction "EXT_EN_60") (pintype "passive+no_connect"))
    )
  )
)
